# mpu-9250.net
KiCad netlist of a schematic drawn in Altium Designer
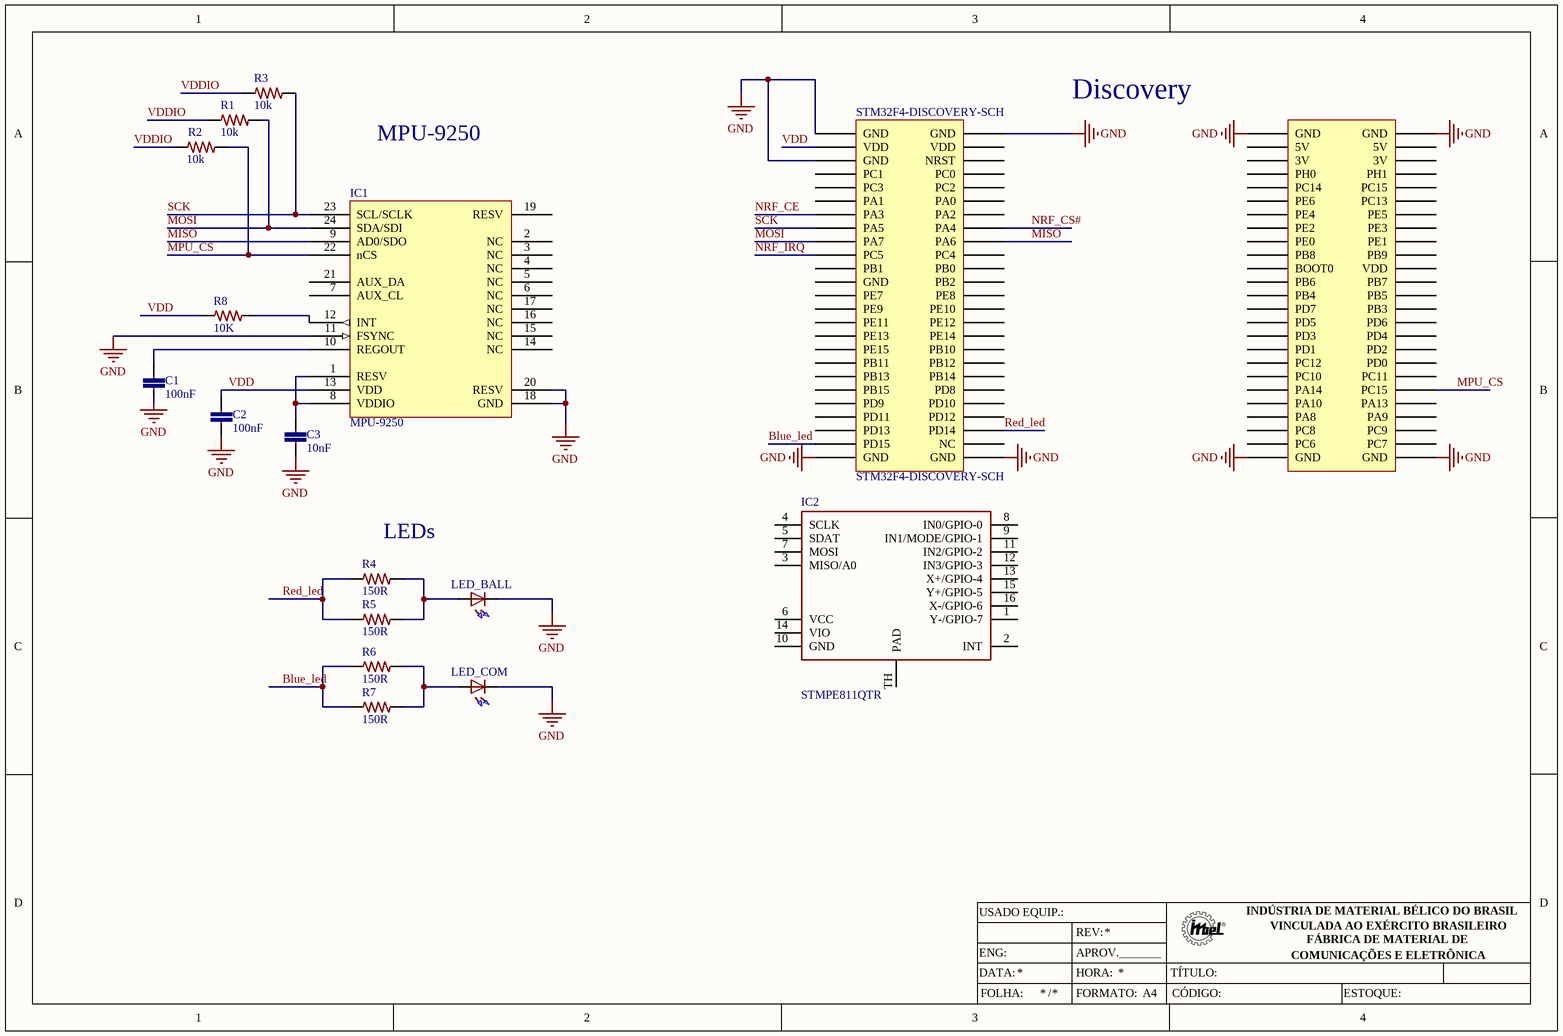
[diagram p0: mpu-9250.SchDoc]

(export (version "E")
  (design (tool "Eeschema 10.0.6"))
  (components
    (comp (ref "C1")
      (value "100nF")
      (footprint "0402-CAP")
      (description "CAP CER 0.1UF 10V 20% X5R 0402")
      (fields (field (name "PART NO") "VJ0402V104ZXQPBC"))
      (libsource (lib "IMBEL") (part "CAPACITOR"))
    )
    (comp (ref "C2")
      (value "100nF")
      (footprint "0402-CAP")
      (description "CAP CER 0.1UF 10V 20% X5R 0402")
      (fields (field (name "PART NO") "VJ0402V104ZXQPBC"))
      (libsource (lib "IMBEL") (part "CAPACITOR"))
    )
    (comp (ref "C3")
      (value "10nF")
      (footprint "0402-CAP")
      (description "CAP CER 10000PF 25V 5% X7R 0402")
      (fields (field (name "PART NO") "GRM155R71E103JA01J"))
      (libsource (lib "IMBEL") (part "CAPACITOR"))
    )
    (comp (ref "IC1")
      (value "MPU-9250")
      (footprint "MPU-9250")
      (description "IMU ACCEL/GYRO/MAG I2C/SPI 24QFN")
      (libsource (lib "IMBEL") (part "Component_1"))
    )
    (comp (ref "IC2")
      (value "STMPE811QTR")
      (footprint "QFN16_N")
      (description "IC TSC I/O EXPAND 8B 16QFN")
      (libsource (lib "IMBEL") (part "STMPE811"))
    )
    (comp (ref "LED_BALL")
      (value "LED")
      (footprint "LED-5MM-PCB")
      (description "LED 5MM PTH")
      (libsource (lib "IMBEL") (part "LED"))
    )
    (comp (ref "LED_COM")
      (value "LED")
      (footprint "LED-5MM-PCB")
      (description "LED 5MM PTH")
      (libsource (lib "IMBEL") (part "LED"))
    )
    (comp (ref "R1")
      (value "10k")
      (footprint "0201-RES")
      (description "RES SMD 10K OHM 1% 1/20W 0201")
      (fields (field (name "PART NO") "ERJ-1GEF1002C"))
      (libsource (lib "IMBEL") (part "RESISTOR"))
    )
    (comp (ref "R2")
      (value "10k")
      (footprint "0201-RES")
      (description "RES SMD 10K OHM 1% 1/20W 0201")
      (fields (field (name "PART NO") "ERJ-1GEF1002C"))
      (libsource (lib "IMBEL") (part "RESISTOR"))
    )
    (comp (ref "R3")
      (value "10k")
      (footprint "0201-RES")
      (description "RES SMD 10K OHM 1% 1/20W 0201")
      (fields (field (name "PART NO") "ERJ-1GEF1002C"))
      (libsource (lib "IMBEL") (part "RESISTOR"))
    )
    (comp (ref "R4")
      (value "150R")
      (footprint "0201-RES")
      (description "RES SMD 150 OHM 1% 1/10W 0402")
      (fields (field (name "PART NO") "ERJ-2RKF1500X"))
      (libsource (lib "IMBEL") (part "RESISTOR"))
    )
    (comp (ref "R5")
      (value "150R")
      (footprint "0201-RES")
      (description "RES SMD 150 OHM 1% 1/10W 0402")
      (fields (field (name "PART NO") "ERJ-2RKF1500X"))
      (libsource (lib "IMBEL") (part "RESISTOR"))
    )
    (comp (ref "R6")
      (value "150R")
      (footprint "0201-RES")
      (description "RES SMD 150 OHM 1% 1/10W 0402")
      (fields (field (name "PART NO") "ERJ-2RKF1500X"))
      (libsource (lib "IMBEL") (part "RESISTOR"))
    )
    (comp (ref "R7")
      (value "150R")
      (footprint "0201-RES")
      (description "RES SMD 150 OHM 1% 1/10W 0402")
      (fields (field (name "PART NO") "ERJ-2RKF1500X"))
      (libsource (lib "IMBEL") (part "RESISTOR"))
    )
    (comp (ref "R8")
      (value "10K")
      (footprint "0402-RES-HD")
      (description "RES 10K OHM 1/10W 1% 0402 SMD")
      (fields (field (name "PART NO") "ERJ-2RKF1002X"))
      (libsource (lib "IMBEL") (part "RESISTOR"))
    )
    (comp (ref "STM32F4-DISCOVERY-SCH")
      (value "STM32F4-DISCOVERY-SCH")
      (footprint "STM32F4-DISCOVERY-PCB")
      (libsource (lib "Schlib1") (part "STM32F4-DISCOVERY-SCH"))
    )
  )
  (nets
    (net (code "1") (name "/Blue_led") (class "Default")
      (node (ref "R6") (pin "1") (pinfunction "1_1") (pintype "passive"))
      (node (ref "R7") (pin "1") (pinfunction "1_1") (pintype "passive"))
      (node (ref "STM32F4-DISCOVERY-SCH") (pin "P1_47") (pinfunction "PD15_P1_47") (pintype "passive"))
    )
    (net (code "2") (name "/MISO") (class "Default")
      (node (ref "IC1") (pin "9") (pinfunction "AD0/SDO_9") (pintype "passive"))
      (node (ref "STM32F4-DISCOVERY-SCH") (pin "P1_18") (pinfunction "PA6_P1_18") (pintype "passive"))
    )
    (net (code "3") (name "/MOSI") (class "Default")
      (node (ref "IC1") (pin "24") (pinfunction "SDA/SDI_24") (pintype "passive"))
      (node (ref "R1") (pin "2") (pinfunction "2_2") (pintype "passive"))
      (node (ref "STM32F4-DISCOVERY-SCH") (pin "P1_17") (pinfunction "PA7_P1_17") (pintype "passive"))
    )
    (net (code "4") (name "/MPU_CS") (class "Default")
      (node (ref "IC1") (pin "22") (pinfunction "nCS_22") (pintype "passive"))
      (node (ref "R2") (pin "2") (pinfunction "2_2") (pintype "passive"))
      (node (ref "STM32F4-DISCOVERY-SCH") (pin "P2_40") (pinfunction "PC15_P2_40") (pintype "passive"))
    )
    (net (code "5") (name "/NRF_CE") (class "Default")
      (node (ref "STM32F4-DISCOVERY-SCH") (pin "P1_13") (pinfunction "PA3_P1_13") (pintype "passive"))
    )
    (net (code "6") (name "/NRF_CS#") (class "Default")
      (node (ref "STM32F4-DISCOVERY-SCH") (pin "P1_16") (pinfunction "PA4_P1_16") (pintype "passive"))
    )
    (net (code "7") (name "/NRF_IRQ") (class "Default")
      (node (ref "STM32F4-DISCOVERY-SCH") (pin "P1_19") (pinfunction "PC5_P1_19") (pintype "passive"))
    )
    (net (code "8") (name "/Red_led") (class "Default")
      (node (ref "R4") (pin "1") (pinfunction "1_1") (pintype "passive"))
      (node (ref "R5") (pin "1") (pinfunction "1_1") (pintype "passive"))
      (node (ref "STM32F4-DISCOVERY-SCH") (pin "P1_46") (pinfunction "PD14_P1_46") (pintype "passive"))
    )
    (net (code "9") (name "/SCK") (class "Default")
      (node (ref "IC1") (pin "23") (pinfunction "SCL/SCLK_23") (pintype "passive"))
      (node (ref "R3") (pin "2") (pinfunction "2_2") (pintype "passive"))
      (node (ref "STM32F4-DISCOVERY-SCH") (pin "P1_15") (pinfunction "PA5_P1_15") (pintype "passive"))
    )
    (net (code "10") (name "/VDD") (class "Default")
      (node (ref "C2") (pin "1") (pinfunction "1_1") (pintype "passive"))
      (node (ref "IC1") (pin "13") (pinfunction "VDD_13") (pintype "power_in"))
      (node (ref "R8") (pin "1") (pinfunction "1_1") (pintype "passive"))
      (node (ref "STM32F4-DISCOVERY-SCH") (pin "P1_3") (pinfunction "VDD_P1_3") (pintype "passive"))
    )
    (net (code "11") (name "/VDDIO") (class "Default")
      (node (ref "R1") (pin "1") (pinfunction "1_1") (pintype "passive"))
      (node (ref "R2") (pin "1") (pinfunction "1_1") (pintype "passive"))
      (node (ref "R3") (pin "1") (pinfunction "1_1") (pintype "passive"))
    )
    (net (code "12") (name "GND") (class "Default")
      (node (ref "C1") (pin "2") (pinfunction "2_2") (pintype "passive"))
      (node (ref "C2") (pin "2") (pinfunction "2_2") (pintype "passive"))
      (node (ref "C3") (pin "2") (pinfunction "2_2") (pintype "passive"))
      (node (ref "IC1") (pin "11") (pinfunction "FSYNC_11") (pintype "input"))
      (node (ref "IC1") (pin "18") (pinfunction "GND_18") (pintype "power_in"))
      (node (ref "IC1") (pin "20") (pinfunction "RESV_20") (pintype "passive"))
      (node (ref "LED_BALL") (pin "1") (pinfunction "K_1") (pintype "passive"))
      (node (ref "LED_COM") (pin "1") (pinfunction "K_1") (pintype "passive"))
      (node (ref "STM32F4-DISCOVERY-SCH") (pin "P1_1") (pinfunction "GND_P1_1") (pintype "passive"))
      (node (ref "STM32F4-DISCOVERY-SCH") (pin "P1_2") (pinfunction "GND_P1_2") (pintype "passive"))
      (node (ref "STM32F4-DISCOVERY-SCH") (pin "P1_49") (pinfunction "GND_P1_49") (pintype "passive"))
      (node (ref "STM32F4-DISCOVERY-SCH") (pin "P1_5") (pinfunction "GND_P1_5") (pintype "passive"))
      (node (ref "STM32F4-DISCOVERY-SCH") (pin "P1_50") (pinfunction "GND_P1_50") (pintype "passive"))
      (node (ref "STM32F4-DISCOVERY-SCH") (pin "P2_1") (pinfunction "GND_P2_1") (pintype "passive"))
      (node (ref "STM32F4-DISCOVERY-SCH") (pin "P2_2") (pinfunction "GND_P2_2") (pintype "passive"))
      (node (ref "STM32F4-DISCOVERY-SCH") (pin "P2_49") (pinfunction "GND_P2_49") (pintype "passive"))
      (node (ref "STM32F4-DISCOVERY-SCH") (pin "P2_50") (pinfunction "GND_P2_50") (pintype "passive"))
    )
    (net (code "13") (name "Net-(IC1-INT)") (class "Default")
      (node (ref "IC1") (pin "12") (pinfunction "INT_12") (pintype "output"))
      (node (ref "R8") (pin "2") (pinfunction "2_2") (pintype "passive"))
    )
    (net (code "14") (name "Net-(IC1-REGOUT)") (class "Default")
      (node (ref "C1") (pin "1") (pinfunction "1_1") (pintype "passive"))
      (node (ref "IC1") (pin "10") (pinfunction "REGOUT_10") (pintype "passive"))
    )
    (net (code "15") (name "Net-(IC1-VDDIO)") (class "Default")
      (node (ref "C3") (pin "1") (pinfunction "1_1") (pintype "passive"))
      (node (ref "IC1") (pin "1") (pinfunction "RESV_1") (pintype "passive"))
      (node (ref "IC1") (pin "8") (pinfunction "VDDIO_8") (pintype "power_in"))
    )
    (net (code "16") (name "Net-(LED_BALL-A)") (class "Default")
      (node (ref "LED_BALL") (pin "2") (pinfunction "A_2") (pintype "passive"))
      (node (ref "R4") (pin "2") (pinfunction "2_2") (pintype "passive"))
      (node (ref "R5") (pin "2") (pinfunction "2_2") (pintype "passive"))
    )
    (net (code "17") (name "Net-(LED_COM-A)") (class "Default")
      (node (ref "LED_COM") (pin "2") (pinfunction "A_2") (pintype "passive"))
      (node (ref "R6") (pin "2") (pinfunction "2_2") (pintype "passive"))
      (node (ref "R7") (pin "2") (pinfunction "2_2") (pintype "passive"))
    )
    (net (code "18") (name "unconnected-(IC1-AUX_CL-Pad7)") (class "Default")
      (node (ref "IC1") (pin "7") (pinfunction "AUX_CL_7") (pintype "passive"))
    )
    (net (code "19") (name "unconnected-(IC1-AUX_DA-Pad21)") (class "Default")
      (node (ref "IC1") (pin "21") (pinfunction "AUX_DA_21") (pintype "passive"))
    )
    (net (code "20") (name "unconnected-(IC1-NC-Pad2)") (class "Default")
      (node (ref "IC1") (pin "2") (pinfunction "NC_2") (pintype "passive"))
    )
    (net (code "21") (name "unconnected-(IC1-NC-Pad3)") (class "Default")
      (node (ref "IC1") (pin "3") (pinfunction "NC_3") (pintype "passive"))
    )
    (net (code "22") (name "unconnected-(IC1-NC-Pad4)") (class "Default")
      (node (ref "IC1") (pin "4") (pinfunction "NC_4") (pintype "passive"))
    )
    (net (code "23") (name "unconnected-(IC1-NC-Pad5)") (class "Default")
      (node (ref "IC1") (pin "5") (pinfunction "NC_5") (pintype "passive"))
    )
    (net (code "24") (name "unconnected-(IC1-NC-Pad6)") (class "Default")
      (node (ref "IC1") (pin "6") (pinfunction "NC_6") (pintype "passive"))
    )
    (net (code "25") (name "unconnected-(IC1-NC-Pad14)") (class "Default")
      (node (ref "IC1") (pin "14") (pinfunction "NC_14") (pintype "passive"))
    )
    (net (code "26") (name "unconnected-(IC1-NC-Pad15)") (class "Default")
      (node (ref "IC1") (pin "15") (pinfunction "NC_15") (pintype "passive"))
    )
    (net (code "27") (name "unconnected-(IC1-NC-Pad16)") (class "Default")
      (node (ref "IC1") (pin "16") (pinfunction "NC_16") (pintype "passive"))
    )
    (net (code "28") (name "unconnected-(IC1-NC-Pad17)") (class "Default")
      (node (ref "IC1") (pin "17") (pinfunction "NC_17") (pintype "passive"))
    )
    (net (code "29") (name "unconnected-(IC1-RESV-Pad19)") (class "Default")
      (node (ref "IC1") (pin "19") (pinfunction "RESV_19") (pintype "passive"))
    )
    (net (code "30") (name "unconnected-(IC2-GND-Pad10)") (class "Default")
      (node (ref "IC2") (pin "10") (pinfunction "GND_10") (pintype "passive"))
    )
    (net (code "31") (name "unconnected-(IC2-IN0{slash}GPIO-0-Pad8)") (class "Default")
      (node (ref "IC2") (pin "8") (pinfunction "IN0/GPIO-0_8") (pintype "passive"))
    )
    (net (code "32") (name "unconnected-(IC2-IN1{slash}MODE{slash}GPIO-1-Pad9)") (class "Default")
      (node (ref "IC2") (pin "9") (pinfunction "IN1/MODE/GPIO-1_9") (pintype "passive"))
    )
    (net (code "33") (name "unconnected-(IC2-IN2{slash}GPIO-2-Pad11)") (class "Default")
      (node (ref "IC2") (pin "11") (pinfunction "IN2/GPIO-2_11") (pintype "passive"))
    )
    (net (code "34") (name "unconnected-(IC2-IN3{slash}GPIO-3-Pad12)") (class "Default")
      (node (ref "IC2") (pin "12") (pinfunction "IN3/GPIO-3_12") (pintype "passive"))
    )
    (net (code "35") (name "unconnected-(IC2-INT-Pad2)") (class "Default")
      (node (ref "IC2") (pin "2") (pinfunction "INT_2") (pintype "passive"))
    )
    (net (code "36") (name "unconnected-(IC2-MISO{slash}A0-Pad3)") (class "Default")
      (node (ref "IC2") (pin "3") (pinfunction "MISO/A0_3") (pintype "passive"))
    )
    (net (code "37") (name "unconnected-(IC2-MOSI-Pad7)") (class "Default")
      (node (ref "IC2") (pin "7") (pinfunction "MOSI_7") (pintype "passive"))
    )
    (net (code "38") (name "unconnected-(IC2-PAD-PadTH)") (class "Default")
      (node (ref "IC2") (pin "TH") (pinfunction "PAD_TH") (pintype "passive"))
    )
    (net (code "39") (name "unconnected-(IC2-SCLK-Pad4)") (class "Default")
      (node (ref "IC2") (pin "4") (pinfunction "SCLK_4") (pintype "passive"))
    )
    (net (code "40") (name "unconnected-(IC2-SDAT-Pad5)") (class "Default")
      (node (ref "IC2") (pin "5") (pinfunction "SDAT_5") (pintype "passive"))
    )
    (net (code "41") (name "unconnected-(IC2-VCC-Pad6)") (class "Default")
      (node (ref "IC2") (pin "6") (pinfunction "VCC_6") (pintype "passive"))
    )
    (net (code "42") (name "unconnected-(IC2-VIO-Pad14)") (class "Default")
      (node (ref "IC2") (pin "14") (pinfunction "VIO_14") (pintype "passive"))
    )
    (net (code "43") (name "unconnected-(IC2-X+{slash}GPIO-4-Pad13)") (class "Default")
      (node (ref "IC2") (pin "13") (pinfunction "X+/GPIO-4_13") (pintype "passive"))
    )
    (net (code "44") (name "unconnected-(IC2-X-{slash}GPIO-6-Pad16)") (class "Default")
      (node (ref "IC2") (pin "16") (pinfunction "X-/GPIO-6_16") (pintype "passive"))
    )
    (net (code "45") (name "unconnected-(IC2-Y+{slash}GPIO-5-Pad15)") (class "Default")
      (node (ref "IC2") (pin "15") (pinfunction "Y+/GPIO-5_15") (pintype "passive"))
    )
    (net (code "46") (name "unconnected-(IC2-Y-{slash}GPIO-7-Pad1)") (class "Default")
      (node (ref "IC2") (pin "1") (pinfunction "Y-/GPIO-7_1") (pintype "passive"))
    )
    (net (code "47") (name "unconnected-(STM32F4-DISCOVERY-SCH-3V-PadP2_5)") (class "Default")
      (node (ref "STM32F4-DISCOVERY-SCH") (pin "P2_5") (pinfunction "3V_P2_5") (pintype "passive"))
    )
    (net (code "48") (name "unconnected-(STM32F4-DISCOVERY-SCH-3V-PadP2_6)") (class "Default")
      (node (ref "STM32F4-DISCOVERY-SCH") (pin "P2_6") (pinfunction "3V_P2_6") (pintype "passive"))
    )
    (net (code "49") (name "unconnected-(STM32F4-DISCOVERY-SCH-5V-PadP2_3)") (class "Default")
      (node (ref "STM32F4-DISCOVERY-SCH") (pin "P2_3") (pinfunction "5V_P2_3") (pintype "passive"))
    )
    (net (code "50") (name "unconnected-(STM32F4-DISCOVERY-SCH-5V-PadP2_4)") (class "Default")
      (node (ref "STM32F4-DISCOVERY-SCH") (pin "P2_4") (pinfunction "5V_P2_4") (pintype "passive"))
    )
    (net (code "51") (name "unconnected-(STM32F4-DISCOVERY-SCH-BOOT0-PadP2_21)") (class "Default")
      (node (ref "STM32F4-DISCOVERY-SCH") (pin "P2_21") (pinfunction "BOOT0_P2_21") (pintype "passive"))
    )
    (net (code "52") (name "unconnected-(STM32F4-DISCOVERY-SCH-GND-PadP1_23)") (class "Default")
      (node (ref "STM32F4-DISCOVERY-SCH") (pin "P1_23") (pinfunction "GND_P1_23") (pintype "passive"))
    )
    (net (code "53") (name "unconnected-(STM32F4-DISCOVERY-SCH-NC-PadP1_48)") (class "Default")
      (node (ref "STM32F4-DISCOVERY-SCH") (pin "P1_48") (pinfunction "NC_P1_48") (pintype "passive"))
    )
    (net (code "54") (name "unconnected-(STM32F4-DISCOVERY-SCH-NRST-PadP1_6)") (class "Default")
      (node (ref "STM32F4-DISCOVERY-SCH") (pin "P1_6") (pinfunction "NRST_P1_6") (pintype "passive"))
    )
    (net (code "55") (name "unconnected-(STM32F4-DISCOVERY-SCH-PA0-PadP1_12)") (class "Default")
      (node (ref "STM32F4-DISCOVERY-SCH") (pin "P1_12") (pinfunction "PA0_P1_12") (pintype "passive"))
    )
    (net (code "56") (name "unconnected-(STM32F4-DISCOVERY-SCH-PA1-PadP1_11)") (class "Default")
      (node (ref "STM32F4-DISCOVERY-SCH") (pin "P1_11") (pinfunction "PA1_P1_11") (pintype "passive"))
    )
    (net (code "57") (name "unconnected-(STM32F4-DISCOVERY-SCH-PA2-PadP1_14)") (class "Default")
      (node (ref "STM32F4-DISCOVERY-SCH") (pin "P1_14") (pinfunction "PA2_P1_14") (pintype "passive"))
    )
    (net (code "58") (name "unconnected-(STM32F4-DISCOVERY-SCH-PA8-PadP2_43)") (class "Default")
      (node (ref "STM32F4-DISCOVERY-SCH") (pin "P2_43") (pinfunction "PA8_P2_43") (pintype "passive"))
    )
    (net (code "59") (name "unconnected-(STM32F4-DISCOVERY-SCH-PA9-PadP2_44)") (class "Default")
      (node (ref "STM32F4-DISCOVERY-SCH") (pin "P2_44") (pinfunction "PA9_P2_44") (pintype "passive"))
    )
    (net (code "60") (name "unconnected-(STM32F4-DISCOVERY-SCH-PA10-PadP2_41)") (class "Default")
      (node (ref "STM32F4-DISCOVERY-SCH") (pin "P2_41") (pinfunction "PA10_P2_41") (pintype "passive"))
    )
    (net (code "61") (name "unconnected-(STM32F4-DISCOVERY-SCH-PA13-PadP2_42)") (class "Default")
      (node (ref "STM32F4-DISCOVERY-SCH") (pin "P2_42") (pinfunction "PA13_P2_42") (pintype "passive"))
    )
    (net (code "62") (name "unconnected-(STM32F4-DISCOVERY-SCH-PA14-PadP2_39)") (class "Default")
      (node (ref "STM32F4-DISCOVERY-SCH") (pin "P2_39") (pinfunction "PA14_P2_39") (pintype "passive"))
    )
    (net (code "63") (name "unconnected-(STM32F4-DISCOVERY-SCH-PB0-PadP1_22)") (class "Default")
      (node (ref "STM32F4-DISCOVERY-SCH") (pin "P1_22") (pinfunction "PB0_P1_22") (pintype "passive"))
    )
    (net (code "64") (name "unconnected-(STM32F4-DISCOVERY-SCH-PB1-PadP1_21)") (class "Default")
      (node (ref "STM32F4-DISCOVERY-SCH") (pin "P1_21") (pinfunction "PB1_P1_21") (pintype "passive"))
    )
    (net (code "65") (name "unconnected-(STM32F4-DISCOVERY-SCH-PB2-PadP1_24)") (class "Default")
      (node (ref "STM32F4-DISCOVERY-SCH") (pin "P1_24") (pinfunction "PB2_P1_24") (pintype "passive"))
    )
    (net (code "66") (name "unconnected-(STM32F4-DISCOVERY-SCH-PB3-PadP2_28)") (class "Default")
      (node (ref "STM32F4-DISCOVERY-SCH") (pin "P2_28") (pinfunction "PB3_P2_28") (pintype "passive"))
    )
    (net (code "67") (name "unconnected-(STM32F4-DISCOVERY-SCH-PB4-PadP2_25)") (class "Default")
      (node (ref "STM32F4-DISCOVERY-SCH") (pin "P2_25") (pinfunction "PB4_P2_25") (pintype "passive"))
    )
    (net (code "68") (name "unconnected-(STM32F4-DISCOVERY-SCH-PB5-PadP2_26)") (class "Default")
      (node (ref "STM32F4-DISCOVERY-SCH") (pin "P2_26") (pinfunction "PB5_P2_26") (pintype "passive"))
    )
    (net (code "69") (name "unconnected-(STM32F4-DISCOVERY-SCH-PB6-PadP2_23)") (class "Default")
      (node (ref "STM32F4-DISCOVERY-SCH") (pin "P2_23") (pinfunction "PB6_P2_23") (pintype "passive"))
    )
    (net (code "70") (name "unconnected-(STM32F4-DISCOVERY-SCH-PB7-PadP1_24)") (class "Default")
      (node (ref "STM32F4-DISCOVERY-SCH") (pin "P1_24") (pinfunction "PB7_P1_24") (pintype "passive"))
    )
    (net (code "71") (name "unconnected-(STM32F4-DISCOVERY-SCH-PB8-PadP2_19)") (class "Default")
      (node (ref "STM32F4-DISCOVERY-SCH") (pin "P2_19") (pinfunction "PB8_P2_19") (pintype "passive"))
    )
    (net (code "72") (name "unconnected-(STM32F4-DISCOVERY-SCH-PB9-PadP2_20)") (class "Default")
      (node (ref "STM32F4-DISCOVERY-SCH") (pin "P2_20") (pinfunction "PB9_P2_20") (pintype "passive"))
    )
    (net (code "73") (name "unconnected-(STM32F4-DISCOVERY-SCH-PB10-PadP1_34)") (class "Default")
      (node (ref "STM32F4-DISCOVERY-SCH") (pin "P1_34") (pinfunction "PB10_P1_34") (pintype "passive"))
    )
    (net (code "74") (name "unconnected-(STM32F4-DISCOVERY-SCH-PB11-PadP1_35)") (class "Default")
      (node (ref "STM32F4-DISCOVERY-SCH") (pin "P1_35") (pinfunction "PB11_P1_35") (pintype "passive"))
    )
    (net (code "75") (name "unconnected-(STM32F4-DISCOVERY-SCH-PB12-PadP1_36)") (class "Default")
      (node (ref "STM32F4-DISCOVERY-SCH") (pin "P1_36") (pinfunction "PB12_P1_36") (pintype "passive"))
    )
    (net (code "76") (name "unconnected-(STM32F4-DISCOVERY-SCH-PB13-PadP1_37)") (class "Default")
      (node (ref "STM32F4-DISCOVERY-SCH") (pin "P1_37") (pinfunction "PB13_P1_37") (pintype "passive"))
    )
    (net (code "77") (name "unconnected-(STM32F4-DISCOVERY-SCH-PB14-PadP1_38)") (class "Default")
      (node (ref "STM32F4-DISCOVERY-SCH") (pin "P1_38") (pinfunction "PB14_P1_38") (pintype "passive"))
    )
    (net (code "78") (name "unconnected-(STM32F4-DISCOVERY-SCH-PB15-PadP1_39)") (class "Default")
      (node (ref "STM32F4-DISCOVERY-SCH") (pin "P1_39") (pinfunction "PB15_P1_39") (pintype "passive"))
    )
    (net (code "79") (name "unconnected-(STM32F4-DISCOVERY-SCH-PC0-PadP1_8)") (class "Default")
      (node (ref "STM32F4-DISCOVERY-SCH") (pin "P1_8") (pinfunction "PC0_P1_8") (pintype "passive"))
    )
    (net (code "80") (name "unconnected-(STM32F4-DISCOVERY-SCH-PC1-PadP1_7)") (class "Default")
      (node (ref "STM32F4-DISCOVERY-SCH") (pin "P1_7") (pinfunction "PC1_P1_7") (pintype "passive"))
    )
    (net (code "81") (name "unconnected-(STM32F4-DISCOVERY-SCH-PC2-PadP1_10)") (class "Default")
      (node (ref "STM32F4-DISCOVERY-SCH") (pin "P1_10") (pinfunction "PC2_P1_10") (pintype "passive"))
    )
    (net (code "82") (name "unconnected-(STM32F4-DISCOVERY-SCH-PC3-PadP1_9)") (class "Default")
      (node (ref "STM32F4-DISCOVERY-SCH") (pin "P1_9") (pinfunction "PC3_P1_9") (pintype "passive"))
    )
    (net (code "83") (name "unconnected-(STM32F4-DISCOVERY-SCH-PC4-PadP1_20)") (class "Default")
      (node (ref "STM32F4-DISCOVERY-SCH") (pin "P1_20") (pinfunction "PC4_P1_20") (pintype "passive"))
    )
    (net (code "84") (name "unconnected-(STM32F4-DISCOVERY-SCH-PC6-PadP2_47)") (class "Default")
      (node (ref "STM32F4-DISCOVERY-SCH") (pin "P2_47") (pinfunction "PC6_P2_47") (pintype "passive"))
    )
    (net (code "85") (name "unconnected-(STM32F4-DISCOVERY-SCH-PC7-PadP2_48)") (class "Default")
      (node (ref "STM32F4-DISCOVERY-SCH") (pin "P2_48") (pinfunction "PC7_P2_48") (pintype "passive"))
    )
    (net (code "86") (name "unconnected-(STM32F4-DISCOVERY-SCH-PC8-PadP2_45)") (class "Default")
      (node (ref "STM32F4-DISCOVERY-SCH") (pin "P2_45") (pinfunction "PC8_P2_45") (pintype "passive"))
    )
    (net (code "87") (name "unconnected-(STM32F4-DISCOVERY-SCH-PC9-PadP2_46)") (class "Default")
      (node (ref "STM32F4-DISCOVERY-SCH") (pin "P2_46") (pinfunction "PC9_P2_46") (pintype "passive"))
    )
    (net (code "88") (name "unconnected-(STM32F4-DISCOVERY-SCH-PC10-PadP2_37)") (class "Default")
      (node (ref "STM32F4-DISCOVERY-SCH") (pin "P2_37") (pinfunction "PC10_P2_37") (pintype "passive"))
    )
    (net (code "89") (name "unconnected-(STM32F4-DISCOVERY-SCH-PC11-PadP2_38)") (class "Default")
      (node (ref "STM32F4-DISCOVERY-SCH") (pin "P2_38") (pinfunction "PC11_P2_38") (pintype "passive"))
    )
    (net (code "90") (name "unconnected-(STM32F4-DISCOVERY-SCH-PC12-PadP2_35)") (class "Default")
      (node (ref "STM32F4-DISCOVERY-SCH") (pin "P2_35") (pinfunction "PC12_P2_35") (pintype "passive"))
    )
    (net (code "91") (name "unconnected-(STM32F4-DISCOVERY-SCH-PC13-PadP2_12)") (class "Default")
      (node (ref "STM32F4-DISCOVERY-SCH") (pin "P2_12") (pinfunction "PC13_P2_12") (pintype "passive"))
    )
    (net (code "92") (name "unconnected-(STM32F4-DISCOVERY-SCH-PC14-PadP2_9)") (class "Default")
      (node (ref "STM32F4-DISCOVERY-SCH") (pin "P2_9") (pinfunction "PC14_P2_9") (pintype "passive"))
    )
    (net (code "93") (name "unconnected-(STM32F4-DISCOVERY-SCH-PC15-PadP2_10)") (class "Default")
      (node (ref "STM32F4-DISCOVERY-SCH") (pin "P2_10") (pinfunction "PC15_P2_10") (pintype "passive"))
    )
    (net (code "94") (name "unconnected-(STM32F4-DISCOVERY-SCH-PD0-PadP2_36)") (class "Default")
      (node (ref "STM32F4-DISCOVERY-SCH") (pin "P2_36") (pinfunction "PD0_P2_36") (pintype "passive"))
    )
    (net (code "95") (name "unconnected-(STM32F4-DISCOVERY-SCH-PD1-PadP2_33)") (class "Default")
      (node (ref "STM32F4-DISCOVERY-SCH") (pin "P2_33") (pinfunction "PD1_P2_33") (pintype "passive"))
    )
    (net (code "96") (name "unconnected-(STM32F4-DISCOVERY-SCH-PD2-PadP1_32)") (class "Default")
      (node (ref "STM32F4-DISCOVERY-SCH") (pin "P1_32") (pinfunction "PD2_P1_32") (pintype "passive"))
    )
    (net (code "97") (name "unconnected-(STM32F4-DISCOVERY-SCH-PD3-PadP2_31)") (class "Default")
      (node (ref "STM32F4-DISCOVERY-SCH") (pin "P2_31") (pinfunction "PD3_P2_31") (pintype "passive"))
    )
    (net (code "98") (name "unconnected-(STM32F4-DISCOVERY-SCH-PD4-PadP2_32)") (class "Default")
      (node (ref "STM32F4-DISCOVERY-SCH") (pin "P2_32") (pinfunction "PD4_P2_32") (pintype "passive"))
    )
    (net (code "99") (name "unconnected-(STM32F4-DISCOVERY-SCH-PD5-PadP2_29)") (class "Default")
      (node (ref "STM32F4-DISCOVERY-SCH") (pin "P2_29") (pinfunction "PD5_P2_29") (pintype "passive"))
    )
    (net (code "100") (name "unconnected-(STM32F4-DISCOVERY-SCH-PD6-PadP2_30)") (class "Default")
      (node (ref "STM32F4-DISCOVERY-SCH") (pin "P2_30") (pinfunction "PD6_P2_30") (pintype "passive"))
    )
    (net (code "101") (name "unconnected-(STM32F4-DISCOVERY-SCH-PD7-PadP2_27)") (class "Default")
      (node (ref "STM32F4-DISCOVERY-SCH") (pin "P2_27") (pinfunction "PD7_P2_27") (pintype "passive"))
    )
    (net (code "102") (name "unconnected-(STM32F4-DISCOVERY-SCH-PD8-PadP1_40)") (class "Default")
      (node (ref "STM32F4-DISCOVERY-SCH") (pin "P1_40") (pinfunction "PD8_P1_40") (pintype "passive"))
    )
    (net (code "103") (name "unconnected-(STM32F4-DISCOVERY-SCH-PD9-PadP1_41)") (class "Default")
      (node (ref "STM32F4-DISCOVERY-SCH") (pin "P1_41") (pinfunction "PD9_P1_41") (pintype "passive"))
    )
    (net (code "104") (name "unconnected-(STM32F4-DISCOVERY-SCH-PD10-PadP1_42)") (class "Default")
      (node (ref "STM32F4-DISCOVERY-SCH") (pin "P1_42") (pinfunction "PD10_P1_42") (pintype "passive"))
    )
    (net (code "105") (name "unconnected-(STM32F4-DISCOVERY-SCH-PD11-PadP1_43)") (class "Default")
      (node (ref "STM32F4-DISCOVERY-SCH") (pin "P1_43") (pinfunction "PD11_P1_43") (pintype "passive"))
    )
    (net (code "106") (name "unconnected-(STM32F4-DISCOVERY-SCH-PD12-PadP1_44)") (class "Default")
      (node (ref "STM32F4-DISCOVERY-SCH") (pin "P1_44") (pinfunction "PD12_P1_44") (pintype "passive"))
    )
    (net (code "107") (name "unconnected-(STM32F4-DISCOVERY-SCH-PD13-PadP1_45)") (class "Default")
      (node (ref "STM32F4-DISCOVERY-SCH") (pin "P1_45") (pinfunction "PD13_P1_45") (pintype "passive"))
    )
    (net (code "108") (name "unconnected-(STM32F4-DISCOVERY-SCH-PE0-PadP2_17)") (class "Default")
      (node (ref "STM32F4-DISCOVERY-SCH") (pin "P2_17") (pinfunction "PE0_P2_17") (pintype "passive"))
    )
    (net (code "109") (name "unconnected-(STM32F4-DISCOVERY-SCH-PE1-PadP2_18)") (class "Default")
      (node (ref "STM32F4-DISCOVERY-SCH") (pin "P2_18") (pinfunction "PE1_P2_18") (pintype "passive"))
    )
    (net (code "110") (name "unconnected-(STM32F4-DISCOVERY-SCH-PE2-PadP2_15)") (class "Default")
      (node (ref "STM32F4-DISCOVERY-SCH") (pin "P2_15") (pinfunction "PE2_P2_15") (pintype "passive"))
    )
    (net (code "111") (name "unconnected-(STM32F4-DISCOVERY-SCH-PE3-PadP2_16)") (class "Default")
      (node (ref "STM32F4-DISCOVERY-SCH") (pin "P2_16") (pinfunction "PE3_P2_16") (pintype "passive"))
    )
    (net (code "112") (name "unconnected-(STM32F4-DISCOVERY-SCH-PE4-PadP2_13)") (class "Default")
      (node (ref "STM32F4-DISCOVERY-SCH") (pin "P2_13") (pinfunction "PE4_P2_13") (pintype "passive"))
    )
    (net (code "113") (name "unconnected-(STM32F4-DISCOVERY-SCH-PE5-PadP2_14)") (class "Default")
      (node (ref "STM32F4-DISCOVERY-SCH") (pin "P2_14") (pinfunction "PE5_P2_14") (pintype "passive"))
    )
    (net (code "114") (name "unconnected-(STM32F4-DISCOVERY-SCH-PE6-PadP2_11)") (class "Default")
      (node (ref "STM32F4-DISCOVERY-SCH") (pin "P2_11") (pinfunction "PE6_P2_11") (pintype "passive"))
    )
    (net (code "115") (name "unconnected-(STM32F4-DISCOVERY-SCH-PE7-PadP1_25)") (class "Default")
      (node (ref "STM32F4-DISCOVERY-SCH") (pin "P1_25") (pinfunction "PE7_P1_25") (pintype "passive"))
    )
    (net (code "116") (name "unconnected-(STM32F4-DISCOVERY-SCH-PE8-PadP1_26)") (class "Default")
      (node (ref "STM32F4-DISCOVERY-SCH") (pin "P1_26") (pinfunction "PE8_P1_26") (pintype "passive"))
    )
    (net (code "117") (name "unconnected-(STM32F4-DISCOVERY-SCH-PE9-PadP1_27)") (class "Default")
      (node (ref "STM32F4-DISCOVERY-SCH") (pin "P1_27") (pinfunction "PE9_P1_27") (pintype "passive"))
    )
    (net (code "118") (name "unconnected-(STM32F4-DISCOVERY-SCH-PE10-PadP1_28)") (class "Default")
      (node (ref "STM32F4-DISCOVERY-SCH") (pin "P1_28") (pinfunction "PE10_P1_28") (pintype "passive"))
    )
    (net (code "119") (name "unconnected-(STM32F4-DISCOVERY-SCH-PE11-PadP1_29)") (class "Default")
      (node (ref "STM32F4-DISCOVERY-SCH") (pin "P1_29") (pinfunction "PE11_P1_29") (pintype "passive"))
    )
    (net (code "120") (name "unconnected-(STM32F4-DISCOVERY-SCH-PE12-PadP1_30)") (class "Default")
      (node (ref "STM32F4-DISCOVERY-SCH") (pin "P1_30") (pinfunction "PE12_P1_30") (pintype "passive"))
    )
    (net (code "121") (name "unconnected-(STM32F4-DISCOVERY-SCH-PE13-PadP1_31)") (class "Default")
      (node (ref "STM32F4-DISCOVERY-SCH") (pin "P1_31") (pinfunction "PE13_P1_31") (pintype "passive"))
    )
    (net (code "122") (name "unconnected-(STM32F4-DISCOVERY-SCH-PE14-PadP1_32)") (class "Default")
      (node (ref "STM32F4-DISCOVERY-SCH") (pin "P1_32") (pinfunction "PE14_P1_32") (pintype "passive"))
    )
    (net (code "123") (name "unconnected-(STM32F4-DISCOVERY-SCH-PE15-PadP1_33)") (class "Default")
      (node (ref "STM32F4-DISCOVERY-SCH") (pin "P1_33") (pinfunction "PE15_P1_33") (pintype "passive"))
    )
    (net (code "124") (name "unconnected-(STM32F4-DISCOVERY-SCH-PH0-PadP2_7)") (class "Default")
      (node (ref "STM32F4-DISCOVERY-SCH") (pin "P2_7") (pinfunction "PH0_P2_7") (pintype "passive"))
    )
    (net (code "125") (name "unconnected-(STM32F4-DISCOVERY-SCH-PH1-PadP2_8)") (class "Default")
      (node (ref "STM32F4-DISCOVERY-SCH") (pin "P2_8") (pinfunction "PH1_P2_8") (pintype "passive"))
    )
    (net (code "126") (name "unconnected-(STM32F4-DISCOVERY-SCH-VDD-PadP2_4)") (class "Default")
      (node (ref "STM32F4-DISCOVERY-SCH") (pin "P2_4") (pinfunction "VDD_P2_4") (pintype "passive"))
    )
    (net (code "127") (name "unconnected-(STM32F4-DISCOVERY-SCH-VDD-PadP2_22)") (class "Default")
      (node (ref "STM32F4-DISCOVERY-SCH") (pin "P2_22") (pinfunction "VDD_P2_22") (pintype "passive"))
    )
  )
)
